# 0126-fetz4-lp.net
KiCad netlist of a schematic drawn in EAGLE
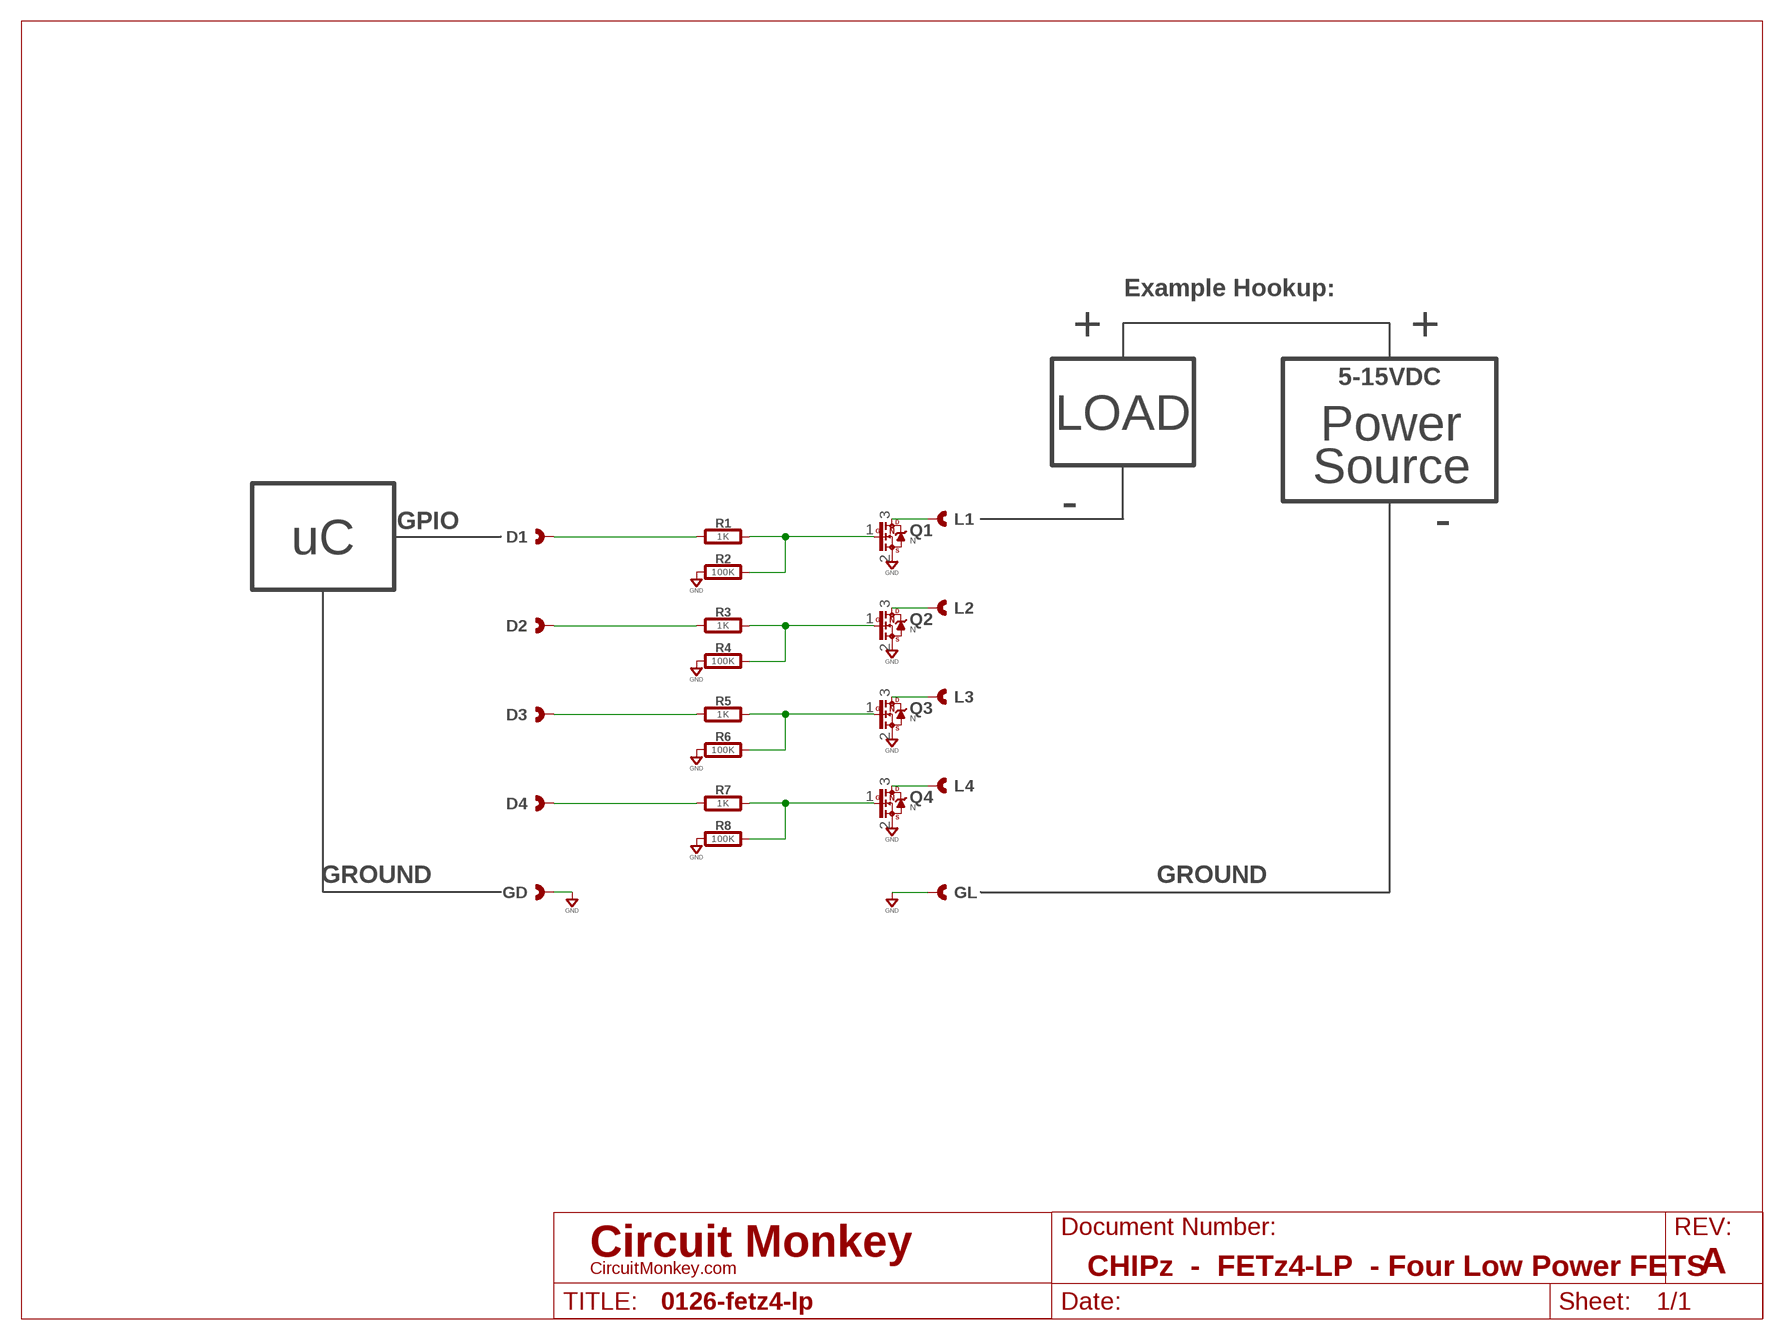
[diagram p0: schematic, sheet 1]

(export (version "E")
  (design (tool "Eeschema 10.0.6"))
  (components
    (comp (ref "D1")
      (value "CAST-01X12.00MM")
      (footprint "eagle-import:CAST01-2.00MM")
      (libsource (lib "eagle-import") (part "CAST-01X12.00MM"))
    )
    (comp (ref "D2")
      (value "CAST-01X12.00MM")
      (footprint "eagle-import:CAST01-2.00MM")
      (libsource (lib "eagle-import") (part "CAST-01X12.00MM"))
    )
    (comp (ref "D3")
      (value "CAST-01X12.00MM")
      (footprint "eagle-import:CAST01-2.00MM")
      (libsource (lib "eagle-import") (part "CAST-01X12.00MM"))
    )
    (comp (ref "D4")
      (value "CAST-01X12.00MM")
      (footprint "eagle-import:CAST01-2.00MM")
      (libsource (lib "eagle-import") (part "CAST-01X12.00MM"))
    )
    (comp (ref "GD")
      (value "CAST-01X12.00MM")
      (footprint "eagle-import:CAST01-2.00MM")
      (libsource (lib "eagle-import") (part "CAST-01X12.00MM"))
    )
    (comp (ref "GL")
      (value "CAST-01X12.00MM")
      (footprint "eagle-import:CAST01-2.00MM")
      (libsource (lib "eagle-import") (part "CAST-01X12.00MM"))
    )
    (comp (ref "L1")
      (value "CAST-01X12.00MM")
      (footprint "eagle-import:CAST01-2.00MM")
      (libsource (lib "eagle-import") (part "CAST-01X12.00MM"))
    )
    (comp (ref "L2")
      (value "CAST-01X12.00MM")
      (footprint "eagle-import:CAST01-2.00MM")
      (libsource (lib "eagle-import") (part "CAST-01X12.00MM"))
    )
    (comp (ref "L3")
      (value "CAST-01X12.00MM")
      (footprint "eagle-import:CAST01-2.00MM")
      (libsource (lib "eagle-import") (part "CAST-01X12.00MM"))
    )
    (comp (ref "L4")
      (value "CAST-01X12.00MM")
      (footprint "eagle-import:CAST01-2.00MM")
      (libsource (lib "eagle-import") (part "CAST-01X12.00MM"))
    )
    (comp (ref "Q1")
      (value "N")
      (footprint "eagle-import:SOT-23")
      (fields (field (name "MPN") "S2318A"))
      (libsource (lib "eagle-import") (part "N-FET_SI2318A"))
    )
    (comp (ref "Q2")
      (value "N")
      (footprint "eagle-import:SOT-23")
      (fields (field (name "MPN") "S2318A"))
      (libsource (lib "eagle-import") (part "N-FET_SI2318A"))
    )
    (comp (ref "Q3")
      (value "N")
      (footprint "eagle-import:SOT-23")
      (fields (field (name "MPN") "S2318A"))
      (libsource (lib "eagle-import") (part "N-FET_SI2318A"))
    )
    (comp (ref "Q4")
      (value "N")
      (footprint "eagle-import:SOT-23")
      (fields (field (name "MPN") "S2318A"))
      (libsource (lib "eagle-import") (part "N-FET_SI2318A"))
    )
    (comp (ref "R1")
      (value "1K")
      (footprint "eagle-import:0603-RES")
      (libsource (lib "eagle-import") (part "RESISTOR0603"))
    )
    (comp (ref "R2")
      (value "100K")
      (footprint "eagle-import:0603-RES")
      (libsource (lib "eagle-import") (part "RESISTOR0603"))
    )
    (comp (ref "R3")
      (value "1K")
      (footprint "eagle-import:0603-RES")
      (libsource (lib "eagle-import") (part "RESISTOR0603"))
    )
    (comp (ref "R4")
      (value "100K")
      (footprint "eagle-import:0603-RES")
      (libsource (lib "eagle-import") (part "RESISTOR0603"))
    )
    (comp (ref "R5")
      (value "1K")
      (footprint "eagle-import:0603-RES")
      (libsource (lib "eagle-import") (part "RESISTOR0603"))
    )
    (comp (ref "R6")
      (value "100K")
      (footprint "eagle-import:0603-RES")
      (libsource (lib "eagle-import") (part "RESISTOR0603"))
    )
    (comp (ref "R7")
      (value "1K")
      (footprint "eagle-import:0603-RES")
      (libsource (lib "eagle-import") (part "RESISTOR0603"))
    )
    (comp (ref "R8")
      (value "100K")
      (footprint "eagle-import:0603-RES")
      (libsource (lib "eagle-import") (part "RESISTOR0603"))
    )
  )
  (nets
    (net (code "1") (name "GND") (class "Default")
      (node (ref "GD") (pin "1") (pinfunction "1_1") (pintype "bidirectional"))
      (node (ref "GD") (pin "P$1") (pinfunction "1_P$1") (pintype "bidirectional"))
      (node (ref "GD") (pin "P$2") (pinfunction "1_P$2") (pintype "bidirectional"))
      (node (ref "GL") (pin "1") (pinfunction "1_1") (pintype "bidirectional"))
      (node (ref "GL") (pin "P$1") (pinfunction "1_P$1") (pintype "bidirectional"))
      (node (ref "GL") (pin "P$2") (pinfunction "1_P$2") (pintype "bidirectional"))
      (node (ref "Q1") (pin "2") (pinfunction "S_2") (pintype "bidirectional"))
      (node (ref "Q2") (pin "2") (pinfunction "S_2") (pintype "bidirectional"))
      (node (ref "Q3") (pin "2") (pinfunction "S_2") (pintype "bidirectional"))
      (node (ref "Q4") (pin "2") (pinfunction "S_2") (pintype "bidirectional"))
      (node (ref "R2") (pin "1") (pinfunction "1_1") (pintype "passive"))
      (node (ref "R4") (pin "1") (pinfunction "1_1") (pintype "passive"))
      (node (ref "R6") (pin "1") (pinfunction "1_1") (pintype "passive"))
      (node (ref "R8") (pin "1") (pinfunction "1_1") (pintype "passive"))
    )
    (net (code "2") (name "Net-(D1-1-PadP$1)") (class "Default")
      (node (ref "D1") (pin "1") (pinfunction "1_1") (pintype "bidirectional"))
      (node (ref "D1") (pin "P$1") (pinfunction "1_P$1") (pintype "bidirectional"))
      (node (ref "D1") (pin "P$2") (pinfunction "1_P$2") (pintype "bidirectional"))
      (node (ref "R1") (pin "1") (pinfunction "1_1") (pintype "passive"))
    )
    (net (code "3") (name "Net-(D2-1-PadP$1)") (class "Default")
      (node (ref "D2") (pin "1") (pinfunction "1_1") (pintype "bidirectional"))
      (node (ref "D2") (pin "P$1") (pinfunction "1_P$1") (pintype "bidirectional"))
      (node (ref "D2") (pin "P$2") (pinfunction "1_P$2") (pintype "bidirectional"))
      (node (ref "R3") (pin "1") (pinfunction "1_1") (pintype "passive"))
    )
    (net (code "4") (name "Net-(D3-1-PadP$1)") (class "Default")
      (node (ref "D3") (pin "1") (pinfunction "1_1") (pintype "bidirectional"))
      (node (ref "D3") (pin "P$1") (pinfunction "1_P$1") (pintype "bidirectional"))
      (node (ref "D3") (pin "P$2") (pinfunction "1_P$2") (pintype "bidirectional"))
      (node (ref "R5") (pin "1") (pinfunction "1_1") (pintype "passive"))
    )
    (net (code "5") (name "Net-(D4-1-PadP$1)") (class "Default")
      (node (ref "D4") (pin "1") (pinfunction "1_1") (pintype "bidirectional"))
      (node (ref "D4") (pin "P$1") (pinfunction "1_P$1") (pintype "bidirectional"))
      (node (ref "D4") (pin "P$2") (pinfunction "1_P$2") (pintype "bidirectional"))
      (node (ref "R7") (pin "1") (pinfunction "1_1") (pintype "passive"))
    )
    (net (code "6") (name "Net-(Q1-D)") (class "Default")
      (node (ref "L1") (pin "1") (pinfunction "1_1") (pintype "bidirectional"))
      (node (ref "L1") (pin "P$1") (pinfunction "1_P$1") (pintype "bidirectional"))
      (node (ref "L1") (pin "P$2") (pinfunction "1_P$2") (pintype "bidirectional"))
      (node (ref "Q1") (pin "3") (pinfunction "D_3") (pintype "bidirectional"))
    )
    (net (code "7") (name "Net-(Q1-G)") (class "Default")
      (node (ref "Q1") (pin "1") (pinfunction "G_1") (pintype "bidirectional"))
      (node (ref "R1") (pin "2") (pinfunction "2_2") (pintype "passive"))
      (node (ref "R2") (pin "2") (pinfunction "2_2") (pintype "passive"))
    )
    (net (code "8") (name "Net-(Q2-D)") (class "Default")
      (node (ref "L2") (pin "1") (pinfunction "1_1") (pintype "bidirectional"))
      (node (ref "L2") (pin "P$1") (pinfunction "1_P$1") (pintype "bidirectional"))
      (node (ref "L2") (pin "P$2") (pinfunction "1_P$2") (pintype "bidirectional"))
      (node (ref "Q2") (pin "3") (pinfunction "D_3") (pintype "bidirectional"))
    )
    (net (code "9") (name "Net-(Q2-G)") (class "Default")
      (node (ref "Q2") (pin "1") (pinfunction "G_1") (pintype "bidirectional"))
      (node (ref "R3") (pin "2") (pinfunction "2_2") (pintype "passive"))
      (node (ref "R4") (pin "2") (pinfunction "2_2") (pintype "passive"))
    )
    (net (code "10") (name "Net-(Q3-D)") (class "Default")
      (node (ref "L3") (pin "1") (pinfunction "1_1") (pintype "bidirectional"))
      (node (ref "L3") (pin "P$1") (pinfunction "1_P$1") (pintype "bidirectional"))
      (node (ref "L3") (pin "P$2") (pinfunction "1_P$2") (pintype "bidirectional"))
      (node (ref "Q3") (pin "3") (pinfunction "D_3") (pintype "bidirectional"))
    )
    (net (code "11") (name "Net-(Q3-G)") (class "Default")
      (node (ref "Q3") (pin "1") (pinfunction "G_1") (pintype "bidirectional"))
      (node (ref "R5") (pin "2") (pinfunction "2_2") (pintype "passive"))
      (node (ref "R6") (pin "2") (pinfunction "2_2") (pintype "passive"))
    )
    (net (code "12") (name "Net-(Q4-D)") (class "Default")
      (node (ref "L4") (pin "1") (pinfunction "1_1") (pintype "bidirectional"))
      (node (ref "L4") (pin "P$1") (pinfunction "1_P$1") (pintype "bidirectional"))
      (node (ref "L4") (pin "P$2") (pinfunction "1_P$2") (pintype "bidirectional"))
      (node (ref "Q4") (pin "3") (pinfunction "D_3") (pintype "bidirectional"))
    )
    (net (code "13") (name "Net-(Q4-G)") (class "Default")
      (node (ref "Q4") (pin "1") (pinfunction "G_1") (pintype "bidirectional"))
      (node (ref "R7") (pin "2") (pinfunction "2_2") (pintype "passive"))
      (node (ref "R8") (pin "2") (pinfunction "2_2") (pintype "passive"))
    )
  )
)
